# DebugBreakout.net
KiCad netlist of a schematic drawn in Altium Designer
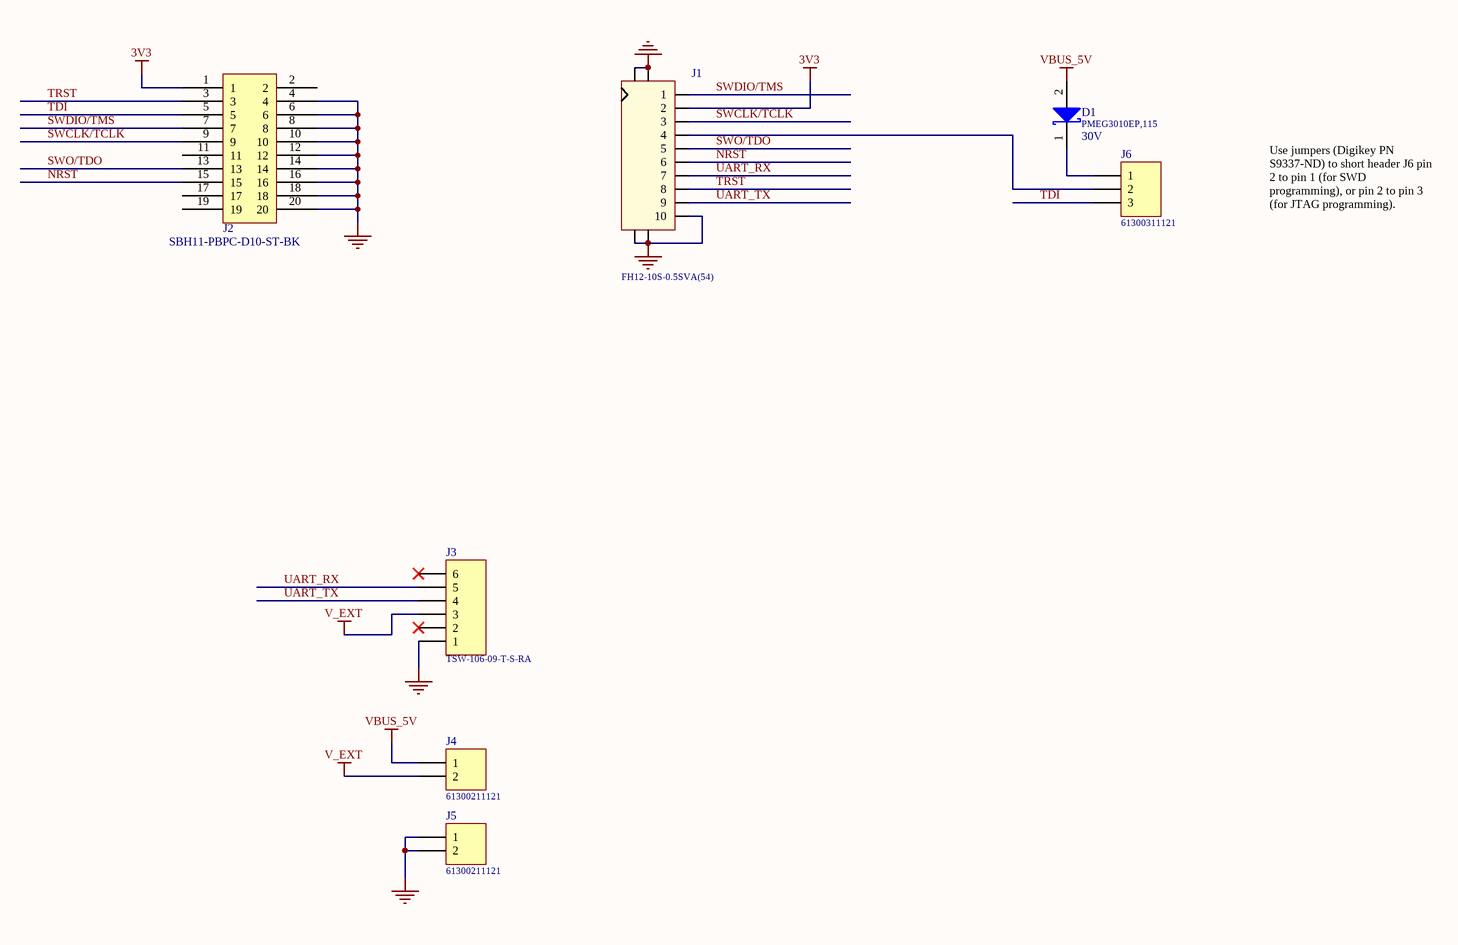
[diagram p0: DebugBreakout.SchDoc]

(export (version "E")
  (design (tool "Eeschema 10.0.6"))
  (components
    (comp (ref "D1")
      (value "PMEG3010EP,115")
      (footprint "DIODE-SOD128")
      (description "DIODE SCHOTTKY 30V 1A SOD128")
      (fields (field (name "BASE PART NUMBER") "PMEG3010") (field (name "REVERSE VOLTAGE") "30V"))
      (libsource (lib "kagwerks") (part "DIODE-SCHOTTKY-30V-1A-SOD128"))
    )
    (comp (ref "J1")
      (value "FH12-10S-0.5SVA(54)")
      (footprint "CONN-V-FPC-10P FH12-10S-0.5SVA(54)")
      (description "CONN FFC VERT 10POS 0.50MM SMD")
      (libsource (lib "kagwerks") (part "CONN-V-FPC-10P-0.5MM"))
    )
    (comp (ref "J2")
      (value "SBH11-PBPC-D10-ST-BK")
      (footprint "HDR-V-2x10-KEYED")
      (description "CONN HEADER VERT 20POS 2.54MM")
      (libsource (lib "kagwerks") (part "HDR-V-2x10-M"))
    )
    (comp (ref "J3")
      (value "TSW-106-09-T-S-RA")
      (footprint "HDR-RA-1X6")
      (description "Conn Unshrouded Header HDR 6 POS 2.54mm Solder RA Thru-Hole Automotive Bulk")
      (libsource (lib "kagwerks") (part "HDR-RA-1X6-M"))
    )
    (comp (ref "J4")
      (value "61300211121")
      (footprint "HDR-V-1X2")
      (description "Header, 2-Pin, 0.1\"")
      (fields (field (name "MANUFACTURER") "Wurth Electronics") (field (name "PUBLISHER") "Altium Limited"))
      (libsource (lib "kagwerks") (part "HDR-V-1X2-M"))
    )
    (comp (ref "J5")
      (value "61300211121")
      (footprint "HDR-V-1X2")
      (description "Header, 2-Pin, 0.1\"")
      (fields (field (name "MANUFACTURER") "Wurth Electronics") (field (name "PUBLISHER") "Altium Limited"))
      (libsource (lib "kagwerks") (part "HDR-V-1X2-M"))
    )
    (comp (ref "J6")
      (value "61300311121")
      (footprint "HDR-V-1X3")
      (description "Header, 3-Pin, 0.1\"")
      (fields (field (name "MANUFACTURER") "Wurth Electronics") (field (name "PUBLISHER") "Altium Limited"))
      (libsource (lib "kagwerks") (part "HDR-V-1X3-M"))
    )
  )
  (nets
    (net (code "1") (name "/NRST") (class "Default")
      (node (ref "J1") (pin "6") (pinfunction "6_6") (pintype "passive"))
      (node (ref "J2") (pin "15") (pinfunction "15_15") (pintype "power_in"))
    )
    (net (code "2") (name "/SWCLK{slash}TCLK") (class "Default")
      (node (ref "J1") (pin "3") (pinfunction "3_3") (pintype "passive"))
      (node (ref "J2") (pin "9") (pinfunction "9_9") (pintype "passive"))
    )
    (net (code "3") (name "/SWDIO{slash}TMS") (class "Default")
      (node (ref "J1") (pin "1") (pinfunction "1_1") (pintype "passive"))
      (node (ref "J2") (pin "7") (pinfunction "7_7") (pintype "passive"))
    )
    (net (code "4") (name "/SWO{slash}TDO") (class "Default")
      (node (ref "J1") (pin "5") (pinfunction "5_5") (pintype "passive"))
      (node (ref "J2") (pin "13") (pinfunction "13_13") (pintype "power_in"))
    )
    (net (code "5") (name "/TDI") (class "Default")
      (node (ref "J2") (pin "5") (pinfunction "5_5") (pintype "passive"))
      (node (ref "J6") (pin "3") (pinfunction "3_3") (pintype "passive"))
    )
    (net (code "6") (name "/TRST") (class "Default")
      (node (ref "J1") (pin "8") (pinfunction "8_8") (pintype "passive"))
      (node (ref "J2") (pin "3") (pinfunction "3_3") (pintype "passive"))
    )
    (net (code "7") (name "/UART_RX") (class "Default")
      (node (ref "J1") (pin "7") (pinfunction "7_7") (pintype "passive"))
      (node (ref "J3") (pin "5") (pinfunction "5_5") (pintype "passive"))
    )
    (net (code "8") (name "/UART_TX") (class "Default")
      (node (ref "J1") (pin "9") (pinfunction "9_9") (pintype "passive"))
      (node (ref "J3") (pin "4") (pinfunction "4_4") (pintype "passive"))
    )
    (net (code "9") (name "3V3") (class "Default")
      (node (ref "J1") (pin "2") (pinfunction "2_2") (pintype "passive"))
      (node (ref "J2") (pin "1") (pinfunction "1_1") (pintype "passive"))
    )
    (net (code "10") (name "GND") (class "Default")
      (node (ref "J1") (pin "10") (pinfunction "10_10") (pintype "passive"))
      (node (ref "J1") (pin "ME1") (pinfunction "ME1_ME1") (pintype "passive"))
      (node (ref "J1") (pin "ME2") (pinfunction "ME2_ME2") (pintype "passive"))
      (node (ref "J1") (pin "ME3") (pinfunction "ME3_ME3") (pintype "passive"))
      (node (ref "J1") (pin "ME4") (pinfunction "ME4_ME4") (pintype "passive"))
      (node (ref "J2") (pin "10") (pinfunction "10_10") (pintype "passive"))
      (node (ref "J2") (pin "12") (pinfunction "12_12") (pintype "power_in"))
      (node (ref "J2") (pin "14") (pinfunction "14_14") (pintype "power_in"))
      (node (ref "J2") (pin "16") (pinfunction "16_16") (pintype "power_in"))
      (node (ref "J2") (pin "18") (pinfunction "18_18") (pintype "power_in"))
      (node (ref "J2") (pin "20") (pinfunction "20_20") (pintype "power_in"))
      (node (ref "J2") (pin "4") (pinfunction "4_4") (pintype "passive"))
      (node (ref "J2") (pin "6") (pinfunction "6_6") (pintype "passive"))
      (node (ref "J2") (pin "8") (pinfunction "8_8") (pintype "passive"))
      (node (ref "J3") (pin "1") (pinfunction "1_1") (pintype "passive"))
      (node (ref "J5") (pin "1") (pinfunction "1_1") (pintype "passive"))
      (node (ref "J5") (pin "2") (pinfunction "2_2") (pintype "passive"))
    )
    (net (code "11") (name "Net-(D1-K)") (class "Default")
      (node (ref "D1") (pin "1") (pinfunction "K_1") (pintype "passive"))
      (node (ref "J6") (pin "1") (pinfunction "1_1") (pintype "passive"))
    )
    (net (code "12") (name "Net-(J1-Pad4)") (class "Default")
      (node (ref "J1") (pin "4") (pinfunction "4_4") (pintype "passive"))
      (node (ref "J6") (pin "2") (pinfunction "2_2") (pintype "passive"))
    )
    (net (code "13") (name "VBUS_5V") (class "Default")
      (node (ref "D1") (pin "2") (pinfunction "A_2") (pintype "passive"))
      (node (ref "J4") (pin "1") (pinfunction "1_1") (pintype "passive"))
    )
    (net (code "14") (name "V_EXT") (class "Default")
      (node (ref "J3") (pin "3") (pinfunction "3_3") (pintype "passive"))
      (node (ref "J4") (pin "2") (pinfunction "2_2") (pintype "passive"))
    )
    (net (code "15") (name "unconnected-(J2-Pad2)") (class "Default")
      (node (ref "J2") (pin "2") (pinfunction "2_2") (pintype "passive"))
    )
    (net (code "16") (name "unconnected-(J2-Pad11)") (class "Default")
      (node (ref "J2") (pin "11") (pinfunction "11_11") (pintype "power_in"))
    )
    (net (code "17") (name "unconnected-(J2-Pad17)") (class "Default")
      (node (ref "J2") (pin "17") (pinfunction "17_17") (pintype "power_in"))
    )
    (net (code "18") (name "unconnected-(J2-Pad19)") (class "Default")
      (node (ref "J2") (pin "19") (pinfunction "19_19") (pintype "power_in"))
    )
    (net (code "19") (name "unconnected-(J3-Pad2)") (class "Default")
      (node (ref "J3") (pin "2") (pinfunction "2_2") (pintype "passive+no_connect"))
    )
    (net (code "20") (name "unconnected-(J3-Pad6)") (class "Default")
      (node (ref "J3") (pin "6") (pinfunction "6_6") (pintype "passive+no_connect"))
    )
  )
)
